# rgb-rotary-encoder-breakout-mk-1_0.net
KiCad netlist of a schematic drawn in EAGLE
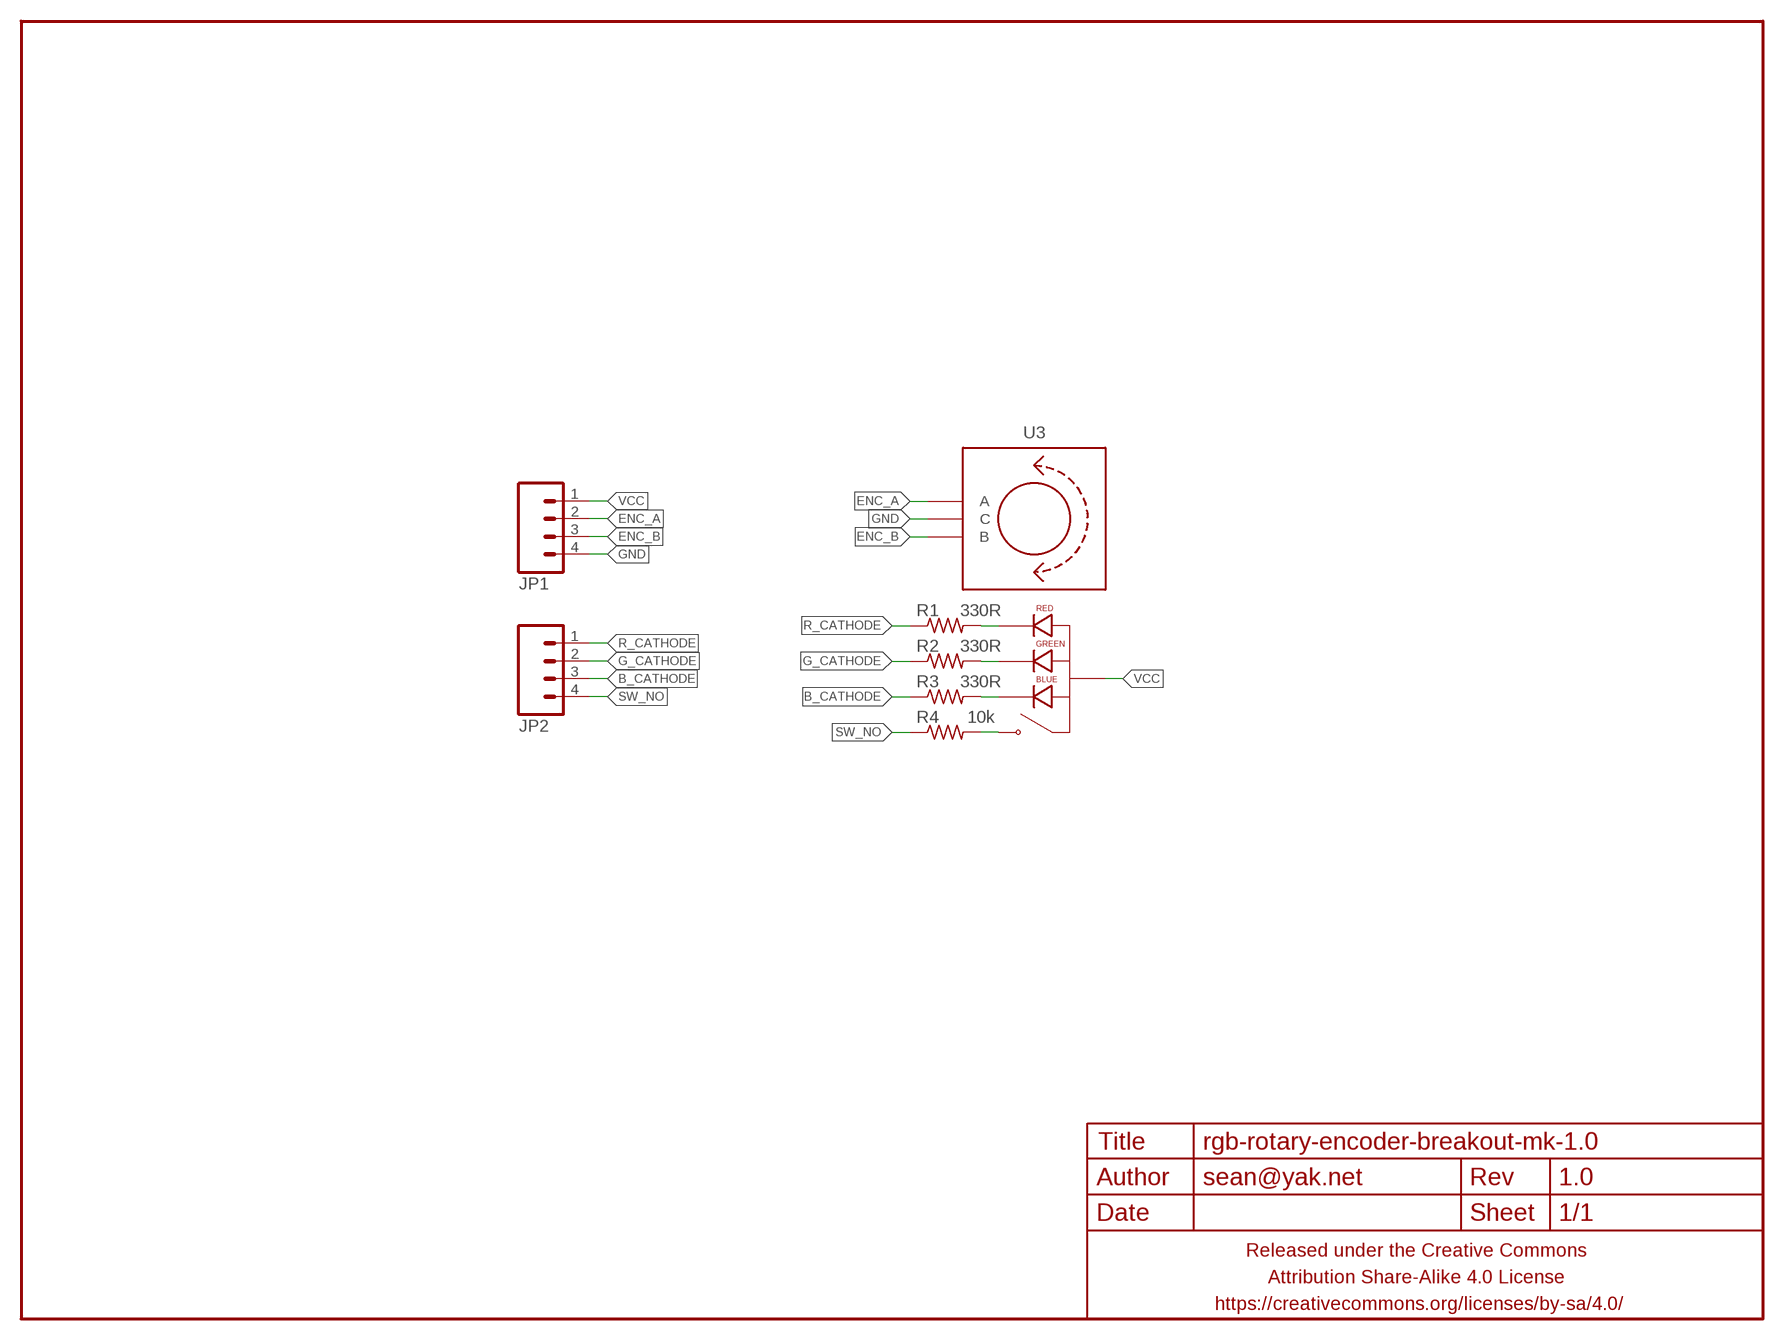
[diagram p0: schematic, sheet 1]

(export (version "E")
  (design (tool "Eeschema 10.0.6"))
  (components
    (comp (ref "FRAME1")
      (value "FRAME-LETTERNO_PACKAGE")
      (footprint "eagle-import:DUMMY")
      (fields (field (name "DESIGNER") "sean@yak.net") (field (name "VERSION") "1.0"))
      (libsource (lib "eagle-import") (part "FRAME-LETTERNO_PACKAGE"))
    )
    (comp (ref "JP1")
      (value "M04PTH")
      (footprint "eagle-import:1X04-PTH-VERT")
      (libsource (lib "eagle-import") (part "M04PTH"))
    )
    (comp (ref "JP2")
      (value "M04PTH")
      (footprint "eagle-import:1X04-PTH-VERT")
      (libsource (lib "eagle-import") (part "M04PTH"))
    )
    (comp (ref "R1")
      (value "330R")
      (footprint "eagle-import:RESISTOR-AXIAL-PTH-7.62MM")
      (libsource (lib "eagle-import") (part "RESISTORPTH-AXIAL-7.62MM"))
    )
    (comp (ref "R2")
      (value "330R")
      (footprint "eagle-import:RESISTOR-AXIAL-PTH-7.62MM")
      (libsource (lib "eagle-import") (part "RESISTORPTH-AXIAL-7.62MM"))
    )
    (comp (ref "R3")
      (value "330R")
      (footprint "eagle-import:RESISTOR-AXIAL-PTH-7.62MM")
      (libsource (lib "eagle-import") (part "RESISTORPTH-AXIAL-7.62MM"))
    )
    (comp (ref "R4")
      (value "10k")
      (footprint "eagle-import:RESISTOR-AXIAL-PTH-7.62MM")
      (libsource (lib "eagle-import") (part "RESISTORPTH-AXIAL-7.62MM"))
    )
    (comp (ref "U3")
      (value "ROTARY_ENCODER_SWITCH_RGBNO_LAB_TOP")
      (footprint "eagle-import:ROTARY_ENCODER_SWITCH_RGB_NO_LAB_TOP")
      (libsource (lib "eagle-import") (part "ROTARY_ENCODER_SWITCH_RGBNO_LAB_TOP"))
    )
  )
  (nets
    (net (code "1") (name "B_CATHODE") (class "Default")
      (node (ref "JP2") (pin "3") (pinfunction "3_3") (pintype "passive"))
      (node (ref "R3") (pin "P$1") (pinfunction "1_P$1") (pintype "passive"))
    )
    (net (code "2") (name "ENC_A") (class "Default")
      (node (ref "JP1") (pin "2") (pinfunction "2_2") (pintype "passive"))
      (node (ref "U3") (pin "ENC_A") (pinfunction "A_ENC_A") (pintype "bidirectional"))
    )
    (net (code "3") (name "ENC_B") (class "Default")
      (node (ref "JP1") (pin "3") (pinfunction "3_3") (pintype "passive"))
      (node (ref "U3") (pin "ENC_B") (pinfunction "B_ENC_B") (pintype "bidirectional"))
    )
    (net (code "4") (name "GND") (class "Default")
      (node (ref "JP1") (pin "4") (pinfunction "4_4") (pintype "passive"))
      (node (ref "U3") (pin "ENC_COM") (pinfunction "C_ENC_COM") (pintype "bidirectional"))
    )
    (net (code "5") (name "G_CATHODE") (class "Default")
      (node (ref "JP2") (pin "2") (pinfunction "2_2") (pintype "passive"))
      (node (ref "R2") (pin "P$1") (pinfunction "1_P$1") (pintype "passive"))
    )
    (net (code "6") (name "Net-(R1-2)") (class "Default")
      (node (ref "R1") (pin "P$2") (pinfunction "2_P$2") (pintype "passive"))
      (node (ref "U3") (pin "LED_R") (pinfunction "RED_CATHODE_LED_R") (pintype "bidirectional"))
    )
    (net (code "7") (name "Net-(R2-2)") (class "Default")
      (node (ref "R2") (pin "P$2") (pinfunction "2_P$2") (pintype "passive"))
      (node (ref "U3") (pin "LED_G") (pinfunction "GREEN_CATHODE_LED_G") (pintype "bidirectional"))
    )
    (net (code "8") (name "Net-(R3-2)") (class "Default")
      (node (ref "R3") (pin "P$2") (pinfunction "2_P$2") (pintype "passive"))
      (node (ref "U3") (pin "LED_B") (pinfunction "BLUE_CATHODE_LED_B") (pintype "bidirectional"))
    )
    (net (code "9") (name "Net-(R4-2)") (class "Default")
      (node (ref "R4") (pin "P$2") (pinfunction "2_P$2") (pintype "passive"))
      (node (ref "U3") (pin "SW_NO") (pinfunction "NO_SW_NO") (pintype "bidirectional"))
    )
    (net (code "10") (name "R_CATHODE") (class "Default")
      (node (ref "JP2") (pin "1") (pinfunction "1_1") (pintype "passive"))
      (node (ref "R1") (pin "P$1") (pinfunction "1_P$1") (pintype "passive"))
    )
    (net (code "11") (name "SW_NO") (class "Default")
      (node (ref "JP2") (pin "4") (pinfunction "4_4") (pintype "passive"))
      (node (ref "R4") (pin "P$1") (pinfunction "1_P$1") (pintype "passive"))
    )
    (net (code "12") (name "VCC") (class "Default")
      (node (ref "JP1") (pin "1") (pinfunction "1_1") (pintype "passive"))
      (node (ref "U3") (pin "LED_SW_COM") (pinfunction "ANODE_LED_SW_COM") (pintype "bidirectional"))
    )
  )
)
